# MaxiSCT-LB.net
KiCad netlist of a schematic drawn in Altium Designer
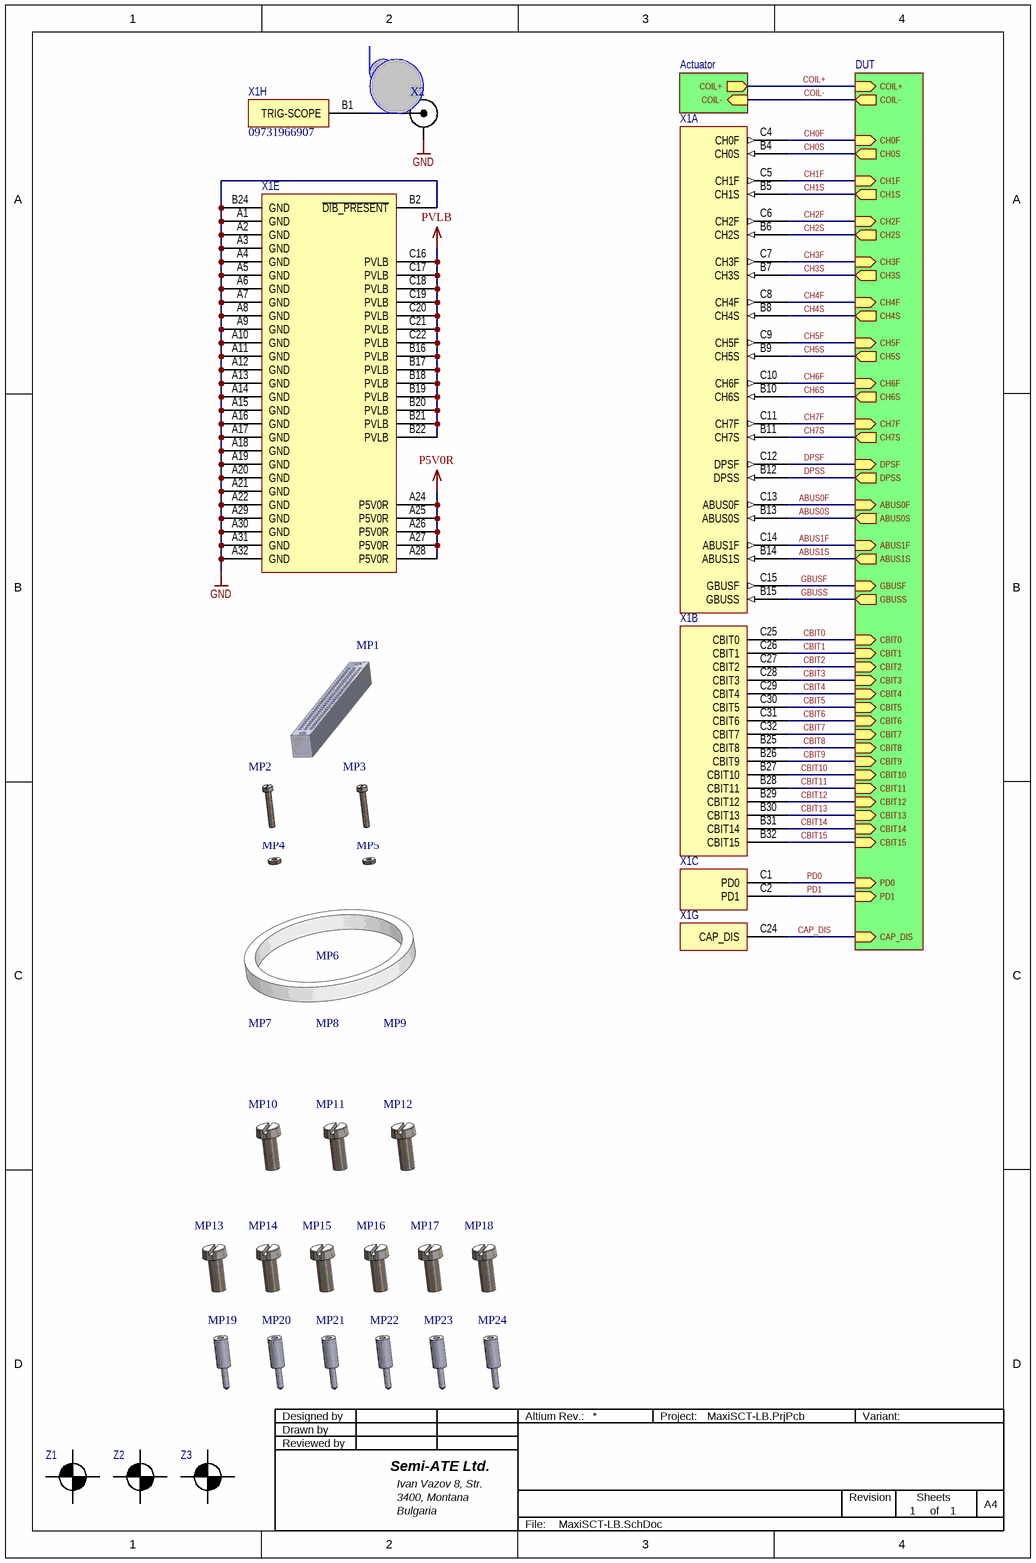
[diagram p0: MaxiSCT-LB.SchDoc]

(export (version "E")
  (design (tool "Eeschema 10.0.6"))
  (components
    (comp (ref "MP1")
      (value "DIN41612 Spacer MiniSCT LB")
      (footprint "Semi-ATE:DIN41612 Spacer MiniSCT LB")
      (description "DIN41612 Spacer LoadBoard side of a MiniSCT")
      (libsource (lib "Mechanical_Parts") (part "DIN41612 Spacer MiniSCT LB"))
    )
    (comp (ref "MP2")
      (value "ISO1207 - M2.5x16")
      (footprint "Semi-ATE:ISO1207 M2.5x16")
      (description "Slotted Cheese Head Screw M2.5x16")
      (libsource (lib "Mechanical_Parts") (part "ISO1207 - M2.5x16"))
    )
    (comp (ref "MP3")
      (value "ISO1207 - M2.5x16")
      (footprint "Semi-ATE:ISO1207 M2.5x16")
      (description "Slotted Cheese Head Screw M2.5x16")
      (libsource (lib "Mechanical_Parts") (part "ISO1207 - M2.5x16"))
    )
    (comp (ref "MP4")
      (value "ISO4035 - M2.5")
      (footprint "Semi-ATE:ISO4035 - M2.5")
      (description "Hex Thin Nut Chamfered grade AB M2.5")
      (libsource (lib "Mechanical_Parts") (part "ISO4035 - M2.5"))
    )
    (comp (ref "MP5")
      (value "ISO4035 - M2.5")
      (footprint "Semi-ATE:ISO4035 - M2.5")
      (description "Hex Thin Nut Chamfered grade AB M2.5")
      (libsource (lib "Mechanical_Parts") (part "ISO4035 - M2.5"))
    )
    (comp (ref "MP6")
      (value "Thermostream Ring")
      (footprint "Semi-ATE:Thermo Stream Ring")
      (libsource (lib "Mechanical_Parts") (part "Thermostream Ring"))
    )
    (comp (ref "MP7")
      (value "Thermostream Dowel")
      (footprint "Semi-ATE:Thermo Dowel")
      (libsource (lib "Mechanical_Parts") (part "Thermostream Dowel"))
    )
    (comp (ref "MP8")
      (value "Thermostream Dowel")
      (footprint "Semi-ATE:Thermo Dowel")
      (libsource (lib "Mechanical_Parts") (part "Thermostream Dowel"))
    )
    (comp (ref "MP9")
      (value "Thermostream Dowel")
      (footprint "Semi-ATE:Thermo Dowel")
      (libsource (lib "Mechanical_Parts") (part "Thermostream Dowel"))
    )
    (comp (ref "MP10")
      (value "ISO1207 - M4x10")
      (footprint "Semi-ATE:ISO1207 M4x10")
      (description "Slotted Cheese Head Screw M4x10")
      (libsource (lib "Mechanical_Parts") (part "ISO1207 - M4x10"))
    )
    (comp (ref "MP11")
      (value "ISO1207 - M4x10")
      (footprint "Semi-ATE:ISO1207 M4x10")
      (description "Slotted Cheese Head Screw M4x10")
      (libsource (lib "Mechanical_Parts") (part "ISO1207 - M4x10"))
    )
    (comp (ref "MP12")
      (value "ISO1207 - M4x10")
      (footprint "Semi-ATE:ISO1207 M4x10")
      (description "Slotted Cheese Head Screw M4x10")
      (libsource (lib "Mechanical_Parts") (part "ISO1207 - M4x10"))
    )
    (comp (ref "MP13")
      (value "ISO1207 - M4x10")
      (footprint "Semi-ATE:ISO1207 M4x10")
      (description "Slotted Cheese Head Screw M4x10")
      (libsource (lib "Mechanical_Parts") (part "ISO1207 - M4x10"))
    )
    (comp (ref "MP14")
      (value "ISO1207 - M4x10")
      (footprint "Semi-ATE:ISO1207 M4x10")
      (description "Slotted Cheese Head Screw M4x10")
      (libsource (lib "Mechanical_Parts") (part "ISO1207 - M4x10"))
    )
    (comp (ref "MP15")
      (value "ISO1207 - M4x10")
      (footprint "Semi-ATE:ISO1207 M4x10")
      (description "Slotted Cheese Head Screw M4x10")
      (libsource (lib "Mechanical_Parts") (part "ISO1207 - M4x10"))
    )
    (comp (ref "MP16")
      (value "ISO1207 - M4x10")
      (footprint "Semi-ATE:ISO1207 M4x10")
      (description "Slotted Cheese Head Screw M4x10")
      (libsource (lib "Mechanical_Parts") (part "ISO1207 - M4x10"))
    )
    (comp (ref "MP17")
      (value "ISO1207 - M4x10")
      (footprint "Semi-ATE:ISO1207 M4x10")
      (description "Slotted Cheese Head Screw M4x10")
      (libsource (lib "Mechanical_Parts") (part "ISO1207 - M4x10"))
    )
    (comp (ref "MP18")
      (value "ISO1207 - M4x10")
      (footprint "Semi-ATE:ISO1207 M4x10")
      (description "Slotted Cheese Head Screw M4x10")
      (libsource (lib "Mechanical_Parts") (part "ISO1207 - M4x10"))
    )
    (comp (ref "MP19")
      (value "MiniSCT LB StandOff")
      (footprint "Semi-ATE:MiniSCT LB StandOff")
      (description "MiniSCT LoadBoard StandOff")
      (libsource (lib "Mechanical_Parts") (part "MiniSCT LB StandOff"))
    )
    (comp (ref "MP20")
      (value "MiniSCT LB StandOff")
      (footprint "Semi-ATE:MiniSCT LB StandOff")
      (description "MiniSCT LoadBoard StandOff")
      (libsource (lib "Mechanical_Parts") (part "MiniSCT LB StandOff"))
    )
    (comp (ref "MP21")
      (value "MiniSCT LB StandOff")
      (footprint "Semi-ATE:MiniSCT LB StandOff")
      (description "MiniSCT LoadBoard StandOff")
      (libsource (lib "Mechanical_Parts") (part "MiniSCT LB StandOff"))
    )
    (comp (ref "MP22")
      (value "MiniSCT LB StandOff")
      (footprint "Semi-ATE:MiniSCT LB StandOff")
      (description "MiniSCT LoadBoard StandOff")
      (libsource (lib "Mechanical_Parts") (part "MiniSCT LB StandOff"))
    )
    (comp (ref "MP23")
      (value "MiniSCT LB StandOff")
      (footprint "Semi-ATE:MiniSCT LB StandOff")
      (description "MiniSCT LoadBoard StandOff")
      (libsource (lib "Mechanical_Parts") (part "MiniSCT LB StandOff"))
    )
    (comp (ref "MP24")
      (value "MiniSCT LB StandOff")
      (footprint "Semi-ATE:MiniSCT LB StandOff")
      (description "MiniSCT LoadBoard StandOff")
      (libsource (lib "Mechanical_Parts") (part "MiniSCT LB StandOff"))
    )
    (comp (ref "X1")
      (value "09731966907")
      (footprint "Semi-ATE:09731966907")
      (description "96 Position Din Connector Header, Male Pins Gold or Gold-Palladium Through Hole")
      (fields (field (name "MANUFACTURER") "Harting"))
      (libsource (lib "Connections") (part "MiniSCT8"))
    )
    (comp (ref "X2")
      (value "112778")
      (footprint "Semi-ATE:112778")
      (description "CONN BNC JACK R/A 75 OHM PCB")
      (fields (field (name "MANUFACTURER") "Amphenol RF"))
      (libsource (lib "Connections") (part "CON_TH_2_F_90_BNC"))
    )
    (comp (ref "Z1")
      (value "Fiducial")
      (footprint "Semi-ATE:Fiducial Cross")
      (description "Assembly AOI")
      (libsource (lib "Miscellaneous") (part "Fiducial"))
    )
    (comp (ref "Z2")
      (value "Fiducial")
      (footprint "Semi-ATE:Fiducial Point")
      (description "Assembly AOI")
      (libsource (lib "Miscellaneous") (part "Fiducial"))
    )
    (comp (ref "Z3")
      (value "Fiducial")
      (footprint "Semi-ATE:Fiducial Cross")
      (description "Assembly AOI")
      (libsource (lib "Miscellaneous") (part "Fiducial"))
    )
  )
  (nets
    (net (code "1") (name "/ABUS0F") (class "Default")
      (node (ref "X1") (pin "C13") (pinfunction "ABUS0F_C13") (pintype "output"))
    )
    (net (code "2") (name "/ABUS0S") (class "Default")
      (node (ref "X1") (pin "B13") (pinfunction "ABUS0S_B13") (pintype "input"))
    )
    (net (code "3") (name "/ABUS1F") (class "Default")
      (node (ref "X1") (pin "C14") (pinfunction "ABUS1F_C14") (pintype "output"))
    )
    (net (code "4") (name "/ABUS1S") (class "Default")
      (node (ref "X1") (pin "B14") (pinfunction "ABUS1S_B14") (pintype "input"))
    )
    (net (code "5") (name "/CAP_DIS") (class "Default")
      (node (ref "X1") (pin "C24") (pinfunction "CAP_DIS_C24") (pintype "passive"))
    )
    (net (code "6") (name "/CBIT0") (class "Default")
      (node (ref "X1") (pin "C25") (pinfunction "CBIT0_C25") (pintype "open_collector"))
    )
    (net (code "7") (name "/CBIT1") (class "Default")
      (node (ref "X1") (pin "C26") (pinfunction "CBIT1_C26") (pintype "open_collector"))
    )
    (net (code "8") (name "/CBIT2") (class "Default")
      (node (ref "X1") (pin "C27") (pinfunction "CBIT2_C27") (pintype "open_collector"))
    )
    (net (code "9") (name "/CBIT3") (class "Default")
      (node (ref "X1") (pin "C28") (pinfunction "CBIT3_C28") (pintype "open_collector"))
    )
    (net (code "10") (name "/CBIT4") (class "Default")
      (node (ref "X1") (pin "C29") (pinfunction "CBIT4_C29") (pintype "open_collector"))
    )
    (net (code "11") (name "/CBIT5") (class "Default")
      (node (ref "X1") (pin "C30") (pinfunction "CBIT5_C30") (pintype "open_collector"))
    )
    (net (code "12") (name "/CBIT6") (class "Default")
      (node (ref "X1") (pin "C31") (pinfunction "CBIT6_C31") (pintype "open_collector"))
    )
    (net (code "13") (name "/CBIT7") (class "Default")
      (node (ref "X1") (pin "C32") (pinfunction "CBIT7_C32") (pintype "open_collector"))
    )
    (net (code "14") (name "/CBIT8") (class "Default")
      (node (ref "X1") (pin "B25") (pinfunction "CBIT8_B25") (pintype "open_collector"))
    )
    (net (code "15") (name "/CBIT9") (class "Default")
      (node (ref "X1") (pin "B26") (pinfunction "CBIT9_B26") (pintype "open_collector"))
    )
    (net (code "16") (name "/CBIT10") (class "Default")
      (node (ref "X1") (pin "B27") (pinfunction "CBIT10_B27") (pintype "open_collector"))
    )
    (net (code "17") (name "/CBIT11") (class "Default")
      (node (ref "X1") (pin "B28") (pinfunction "CBIT11_B28") (pintype "open_collector"))
    )
    (net (code "18") (name "/CBIT12") (class "Default")
      (node (ref "X1") (pin "B29") (pinfunction "CBIT12_B29") (pintype "open_collector"))
    )
    (net (code "19") (name "/CBIT13") (class "Default")
      (node (ref "X1") (pin "B30") (pinfunction "CBIT13_B30") (pintype "open_collector"))
    )
    (net (code "20") (name "/CBIT14") (class "Default")
      (node (ref "X1") (pin "B31") (pinfunction "CBIT14_B31") (pintype "open_collector"))
    )
    (net (code "21") (name "/CBIT15") (class "Default")
      (node (ref "X1") (pin "B32") (pinfunction "CBIT15_B32") (pintype "open_collector"))
    )
    (net (code "22") (name "/CH0F") (class "Default")
      (node (ref "X1") (pin "C4") (pinfunction "CH0F_C4") (pintype "output"))
    )
    (net (code "23") (name "/CH0S") (class "Default")
      (node (ref "X1") (pin "B4") (pinfunction "CH0S_B4") (pintype "input"))
    )
    (net (code "24") (name "/CH1F") (class "Default")
      (node (ref "X1") (pin "C5") (pinfunction "CH1F_C5") (pintype "output"))
    )
    (net (code "25") (name "/CH1S") (class "Default")
      (node (ref "X1") (pin "B5") (pinfunction "CH1S_B5") (pintype "input"))
    )
    (net (code "26") (name "/CH2F") (class "Default")
      (node (ref "X1") (pin "C6") (pinfunction "CH2F_C6") (pintype "output"))
    )
    (net (code "27") (name "/CH2S") (class "Default")
      (node (ref "X1") (pin "B6") (pinfunction "CH2S_B6") (pintype "input"))
    )
    (net (code "28") (name "/CH3F") (class "Default")
      (node (ref "X1") (pin "C7") (pinfunction "CH3F_C7") (pintype "output"))
    )
    (net (code "29") (name "/CH3S") (class "Default")
      (node (ref "X1") (pin "B7") (pinfunction "CH3S_B7") (pintype "input"))
    )
    (net (code "30") (name "/CH4F") (class "Default")
      (node (ref "X1") (pin "C8") (pinfunction "CH4F_C8") (pintype "output"))
    )
    (net (code "31") (name "/CH4S") (class "Default")
      (node (ref "X1") (pin "B8") (pinfunction "CH4S_B8") (pintype "input"))
    )
    (net (code "32") (name "/CH5F") (class "Default")
      (node (ref "X1") (pin "C9") (pinfunction "CH5F_C9") (pintype "output"))
    )
    (net (code "33") (name "/CH5S") (class "Default")
      (node (ref "X1") (pin "B9") (pinfunction "CH5S_B9") (pintype "input"))
    )
    (net (code "34") (name "/CH6F") (class "Default")
      (node (ref "X1") (pin "C10") (pinfunction "CH6F_C10") (pintype "output"))
    )
    (net (code "35") (name "/CH6S") (class "Default")
      (node (ref "X1") (pin "B10") (pinfunction "CH6S_B10") (pintype "input"))
    )
    (net (code "36") (name "/CH7F") (class "Default")
      (node (ref "X1") (pin "C11") (pinfunction "CH7F_C11") (pintype "output"))
    )
    (net (code "37") (name "/CH7S") (class "Default")
      (node (ref "X1") (pin "B11") (pinfunction "CH7S_B11") (pintype "input"))
    )
    (net (code "40") (name "/DPSF") (class "Default")
      (node (ref "X1") (pin "C12") (pinfunction "DPSF_C12") (pintype "output"))
    )
    (net (code "41") (name "/DPSS") (class "Default")
      (node (ref "X1") (pin "B12") (pinfunction "DPSS_B12") (pintype "input"))
    )
    (net (code "42") (name "/GBUSF") (class "Default")
      (node (ref "X1") (pin "C15") (pinfunction "GBUSF_C15") (pintype "output"))
    )
    (net (code "43") (name "/GBUSS") (class "Default")
      (node (ref "X1") (pin "B15") (pinfunction "GBUSS_B15") (pintype "input"))
    )
    (net (code "44") (name "/PD0") (class "Default")
      (node (ref "X1") (pin "C1") (pinfunction "PD0_C1") (pintype "passive"))
    )
    (net (code "45") (name "/PD1") (class "Default")
      (node (ref "X1") (pin "C2") (pinfunction "PD1_C2") (pintype "passive"))
    )
    (net (code "46") (name "GND") (class "Default")
      (node (ref "X1") (pin "A1") (pinfunction "GND_A1") (pintype "passive"))
      (node (ref "X1") (pin "A10") (pinfunction "GND_A10") (pintype "passive"))
      (node (ref "X1") (pin "A11") (pinfunction "GND_A11") (pintype "passive"))
      (node (ref "X1") (pin "A12") (pinfunction "GND_A12") (pintype "passive"))
      (node (ref "X1") (pin "A13") (pinfunction "GND_A13") (pintype "passive"))
      (node (ref "X1") (pin "A14") (pinfunction "GND_A14") (pintype "passive"))
      (node (ref "X1") (pin "A15") (pinfunction "GND_A15") (pintype "passive"))
      (node (ref "X1") (pin "A16") (pinfunction "GND_A16") (pintype "passive"))
      (node (ref "X1") (pin "A17") (pinfunction "GND_A17") (pintype "passive"))
      (node (ref "X1") (pin "A18") (pinfunction "GND_A18") (pintype "passive"))
      (node (ref "X1") (pin "A19") (pinfunction "GND_A19") (pintype "passive"))
      (node (ref "X1") (pin "A2") (pinfunction "GND_A2") (pintype "passive"))
      (node (ref "X1") (pin "A20") (pinfunction "GND_A20") (pintype "passive"))
      (node (ref "X1") (pin "A21") (pinfunction "GND_A21") (pintype "passive"))
      (node (ref "X1") (pin "A22") (pinfunction "GND_A22") (pintype "passive"))
      (node (ref "X1") (pin "A29") (pinfunction "GND_A29") (pintype "passive"))
      (node (ref "X1") (pin "A3") (pinfunction "GND_A3") (pintype "passive"))
      (node (ref "X1") (pin "A30") (pinfunction "GND_A30") (pintype "passive"))
      (node (ref "X1") (pin "A31") (pinfunction "GND_A31") (pintype "passive"))
      (node (ref "X1") (pin "A32") (pinfunction "GND_A32") (pintype "passive"))
      (node (ref "X1") (pin "A4") (pinfunction "GND_A4") (pintype "passive"))
      (node (ref "X1") (pin "A5") (pinfunction "GND_A5") (pintype "passive"))
      (node (ref "X1") (pin "A6") (pinfunction "GND_A6") (pintype "passive"))
      (node (ref "X1") (pin "A7") (pinfunction "GND_A7") (pintype "passive"))
      (node (ref "X1") (pin "A8") (pinfunction "GND_A8") (pintype "passive"))
      (node (ref "X1") (pin "A9") (pinfunction "GND_A9") (pintype "passive"))
      (node (ref "X1") (pin "B2") (pinfunction "~{DIB_PRESENT}_B2") (pintype "passive"))
      (node (ref "X1") (pin "B24") (pinfunction "GND_B24") (pintype "passive"))
      (node (ref "X2") (pin "0") (pinfunction "Shield_0") (pintype "passive"))
    )
    (net (code "47") (name "Net-(X1H-TRIG-SCOPE)") (class "Default")
      (node (ref "X1") (pin "B1") (pinfunction "TRIG-SCOPE_B1") (pintype "passive"))
      (node (ref "X2") (pin "1") (pinfunction "Signal_1") (pintype "passive"))
    )
    (net (code "48") (name "P5V0R") (class "Default")
      (node (ref "X1") (pin "A24") (pinfunction "P5V0R_A24") (pintype "passive"))
      (node (ref "X1") (pin "A25") (pinfunction "P5V0R_A25") (pintype "passive"))
      (node (ref "X1") (pin "A26") (pinfunction "P5V0R_A26") (pintype "passive"))
      (node (ref "X1") (pin "A27") (pinfunction "P5V0R_A27") (pintype "passive"))
      (node (ref "X1") (pin "A28") (pinfunction "P5V0R_A28") (pintype "passive"))
    )
    (net (code "49") (name "PVLB") (class "Default")
      (node (ref "X1") (pin "B16") (pinfunction "PVLB_B16") (pintype "passive"))
      (node (ref "X1") (pin "B17") (pinfunction "PVLB_B17") (pintype "passive"))
      (node (ref "X1") (pin "B18") (pinfunction "PVLB_B18") (pintype "passive"))
      (node (ref "X1") (pin "B19") (pinfunction "PVLB_B19") (pintype "passive"))
      (node (ref "X1") (pin "B20") (pinfunction "PVLB_B20") (pintype "passive"))
      (node (ref "X1") (pin "B21") (pinfunction "PVLB_B21") (pintype "passive"))
      (node (ref "X1") (pin "B22") (pinfunction "PVLB_B22") (pintype "passive"))
      (node (ref "X1") (pin "C16") (pinfunction "PVLB_C16") (pintype "passive"))
      (node (ref "X1") (pin "C17") (pinfunction "PVLB_C17") (pintype "passive"))
      (node (ref "X1") (pin "C18") (pinfunction "PVLB_C18") (pintype "passive"))
      (node (ref "X1") (pin "C19") (pinfunction "PVLB_C19") (pintype "passive"))
      (node (ref "X1") (pin "C20") (pinfunction "PVLB_C20") (pintype "passive"))
      (node (ref "X1") (pin "C21") (pinfunction "PVLB_C21") (pintype "passive"))
      (node (ref "X1") (pin "C22") (pinfunction "PVLB_C22") (pintype "passive"))
    )
  )
)
